# 0_Overview.net
KiCad netlist of a schematic drawn in Altium Designer
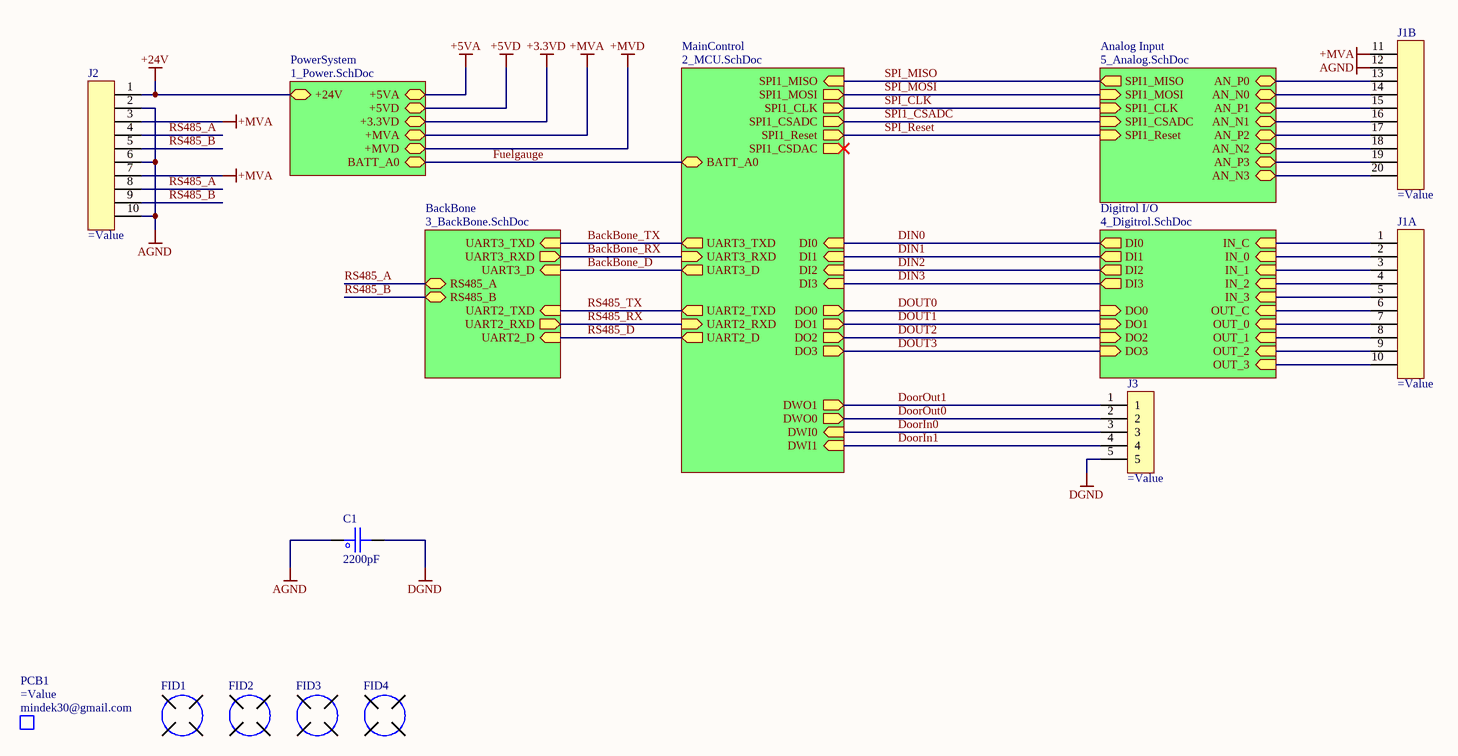
[diagram p0: 0_Overview.SchDoc]

(export (version "E")
  (design (tool "Eeschema 10.0.6"))
  (components
    (comp (ref "C1")
      (value "2200pF")
      (footprint "C_1206")
      (description "CAP CER 2200PF 1KV X7R 1206")
      (fields (field (name "MANUFACTURER") "AVX Corporation") (field (name "PARTNUMBER") "1206AC222KAT1A"))
      (libsource (lib "UUSymbol") (part "C_Capacitor"))
    )
    (comp (ref "FID1")
      (value "FIDUCIAL")
      (footprint "FID")
      (description "Fiducial")
      (fields (field (name "MANUFACTURER") "mindek30@gmail.com") (field (name "PARTNUMBER") "_"))
      (libsource (lib "UUSymbol") (part "FID_FIDUCIAL"))
    )
    (comp (ref "FID2")
      (value "FIDUCIAL")
      (footprint "FID")
      (description "Fiducial")
      (fields (field (name "MANUFACTURER") "mindek30@gmail.com") (field (name "PARTNUMBER") "_"))
      (libsource (lib "UUSymbol") (part "FID_FIDUCIAL"))
    )
    (comp (ref "FID3")
      (value "FIDUCIAL")
      (footprint "FID")
      (description "Fiducial")
      (fields (field (name "MANUFACTURER") "mindek30@gmail.com") (field (name "PARTNUMBER") "_"))
      (libsource (lib "UUSymbol") (part "FID_FIDUCIAL"))
    )
    (comp (ref "FID4")
      (value "FIDUCIAL")
      (footprint "FID")
      (description "Fiducial")
      (fields (field (name "MANUFACTURER") "mindek30@gmail.com") (field (name "PARTNUMBER") "_"))
      (libsource (lib "UUSymbol") (part "FID_FIDUCIAL"))
    )
    (comp (ref "J1")
      (value "~")
      (footprint "CON_20P_Terminal")
      (description "TERM BLOCK HDR 20POS 90DEG 3.5MM")
      (fields (field (name "PARTNUMBER") "KF2EDGK-20P"))
      (libsource (lib "UUSymbol") (part "CON_20P_Terminal"))
    )
    (comp (ref "J2")
      (value "~")
      (footprint "CON_10P_Terminal")
      (description "TERM BLOCK HDR 10POS 90DEG 3.5MM")
      (fields (field (name "PARTNUMBER") "KF2EDGK-10P"))
      (libsource (lib "UUSymbol") (part "CON_10P_Terminal"))
    )
    (comp (ref "J3")
      (value "~")
      (footprint "MOLEX_532610571")
      (description "CONN HEADER SMD R/A 5POS 1.25MM")
      (fields (field (name "PARTNUMBER") "0532610571") (field (name "MANUFACTURER") "Molex"))
      (libsource (lib "UUSymbol") (part "CON_5P_532610571"))
    )
    (comp (ref "PCB1")
      (value "~")
      (description "BARE PCB")
      (fields (field (name "MANUFACTURER") "mindek30@gmail.com") (field (name "PARTNUMBER") "_"))
      (libsource (lib "UUSymbol") (part "PCB_Bare"))
    )
  )
  (nets
    (net (code "4") (name "+24V") (class "Default")
      (node (ref "J2") (pin "1") (pinfunction "1_1") (pintype "passive"))
    )
    (net (code "5") (name "+MVA") (class "Default")
      (node (ref "J1") (pin "11") (pinfunction "11_11") (pintype "passive"))
      (node (ref "J2") (pin "3") (pinfunction "3_3") (pintype "passive"))
      (node (ref "J2") (pin "7") (pinfunction "7_7") (pintype "passive"))
    )
    (net (code "7") (name "/AN_N0") (class "Default")
      (node (ref "J1") (pin "14") (pinfunction "14_14") (pintype "passive"))
    )
    (net (code "8") (name "/AN_N1") (class "Default")
      (node (ref "J1") (pin "16") (pinfunction "16_16") (pintype "passive"))
    )
    (net (code "9") (name "/AN_N2") (class "Default")
      (node (ref "J1") (pin "18") (pinfunction "18_18") (pintype "passive"))
    )
    (net (code "10") (name "/AN_N3") (class "Default")
      (node (ref "J1") (pin "20") (pinfunction "20_20") (pintype "passive"))
    )
    (net (code "11") (name "/AN_P0") (class "Default")
      (node (ref "J1") (pin "13") (pinfunction "13_13") (pintype "passive"))
    )
    (net (code "12") (name "/AN_P1") (class "Default")
      (node (ref "J1") (pin "15") (pinfunction "15_15") (pintype "passive"))
    )
    (net (code "13") (name "/AN_P2") (class "Default")
      (node (ref "J1") (pin "17") (pinfunction "17_17") (pintype "passive"))
    )
    (net (code "14") (name "/AN_P3") (class "Default")
      (node (ref "J1") (pin "19") (pinfunction "19_19") (pintype "passive"))
    )
    (net (code "26") (name "/DoorIn0") (class "Default")
      (node (ref "J3") (pin "3") (pinfunction "3_3") (pintype "passive"))
    )
    (net (code "27") (name "/DoorIn1") (class "Default")
      (node (ref "J3") (pin "4") (pinfunction "4_4") (pintype "passive"))
    )
    (net (code "28") (name "/DoorOut0") (class "Default")
      (node (ref "J3") (pin "2") (pinfunction "2_2") (pintype "passive"))
    )
    (net (code "29") (name "/DoorOut1") (class "Default")
      (node (ref "J3") (pin "1") (pinfunction "1_1") (pintype "passive"))
    )
    (net (code "31") (name "/IN_0") (class "Default")
      (node (ref "J1") (pin "2") (pinfunction "2_2") (pintype "passive"))
    )
    (net (code "32") (name "/IN_1") (class "Default")
      (node (ref "J1") (pin "3") (pinfunction "3_3") (pintype "passive"))
    )
    (net (code "33") (name "/IN_2") (class "Default")
      (node (ref "J1") (pin "4") (pinfunction "4_4") (pintype "passive"))
    )
    (net (code "34") (name "/IN_3") (class "Default")
      (node (ref "J1") (pin "5") (pinfunction "5_5") (pintype "passive"))
    )
    (net (code "35") (name "/IN_C") (class "Default")
      (node (ref "J1") (pin "1") (pinfunction "1_1") (pintype "passive"))
    )
    (net (code "36") (name "/OUT_0") (class "Default")
      (node (ref "J1") (pin "7") (pinfunction "7_7") (pintype "passive"))
    )
    (net (code "37") (name "/OUT_1") (class "Default")
      (node (ref "J1") (pin "8") (pinfunction "8_8") (pintype "passive"))
    )
    (net (code "38") (name "/OUT_2") (class "Default")
      (node (ref "J1") (pin "9") (pinfunction "9_9") (pintype "passive"))
    )
    (net (code "39") (name "/OUT_3") (class "Default")
      (node (ref "J1") (pin "10") (pinfunction "10_10") (pintype "passive"))
    )
    (net (code "40") (name "/OUT_C") (class "Default")
      (node (ref "J1") (pin "6") (pinfunction "6_6") (pintype "passive"))
    )
    (net (code "41") (name "/RS485_A") (class "Default")
      (node (ref "J2") (pin "4") (pinfunction "4_4") (pintype "passive"))
      (node (ref "J2") (pin "8") (pinfunction "8_8") (pintype "passive"))
    )
    (net (code "42") (name "/RS485_B") (class "Default")
      (node (ref "J2") (pin "5") (pinfunction "5_5") (pintype "passive"))
      (node (ref "J2") (pin "9") (pinfunction "9_9") (pintype "passive"))
    )
    (net (code "52") (name "AGND") (class "Default")
      (node (ref "C1") (pin "1") (pinfunction "1_1") (pintype "passive"))
      (node (ref "J1") (pin "12") (pinfunction "12_12") (pintype "passive"))
      (node (ref "J2") (pin "10") (pinfunction "10_10") (pintype "passive"))
      (node (ref "J2") (pin "2") (pinfunction "2_2") (pintype "passive"))
      (node (ref "J2") (pin "6") (pinfunction "6_6") (pintype "passive"))
    )
    (net (code "53") (name "DGND") (class "Default")
      (node (ref "C1") (pin "2") (pinfunction "2_2") (pintype "passive"))
      (node (ref "J3") (pin "5") (pinfunction "5_5") (pintype "passive"))
    )
  )
)
